# ps2st_mouse_v3.net
KiCad netlist of a schematic drawn in EAGLE
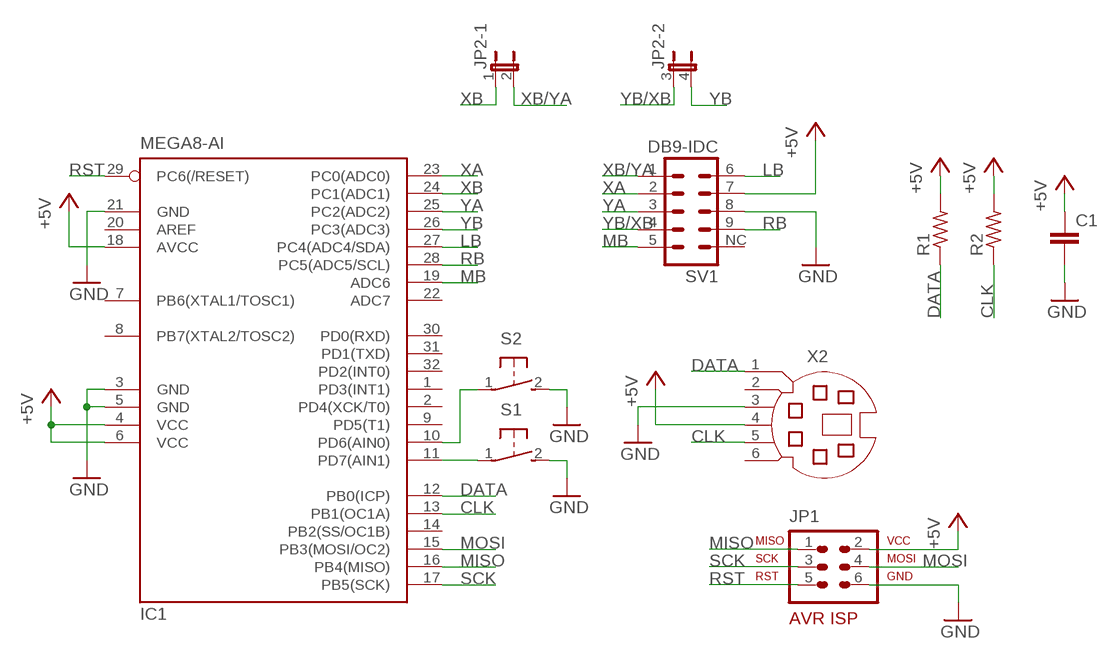
[diagram p0: schematic, sheet 1]

(export (version "E")
  (design (tool "Eeschema 10.0.6"))
  (components
    (comp (ref "C1")
      (value "C-EUC0805")
      (footprint "eagle-import:C0805")
      (libsource (lib "eagle-import") (part "C-EUC0805"))
    )
    (comp (ref "IC1")
      (value "MEGA8-AI")
      (footprint "eagle-import:TQFP32-08")
      (fields (field (name "MPN") "ATMEGA8-16AU"))
      (libsource (lib "eagle-import") (part "MEGA8-AI"))
    )
    (comp (ref "JP1")
      (value "AVR-ISP-6VERT")
      (footprint "eagle-import:AVR-ISP-6")
      (libsource (lib "eagle-import") (part "AVR-ISP-6VERT"))
    )
    (comp (ref "JP2")
      (value "JP2QE")
      (footprint "eagle-import:JP2Q")
      (libsource (lib "eagle-import") (part "JP2QE"))
    )
    (comp (ref "R1")
      (value "R-US_R0805")
      (footprint "eagle-import:R0805")
      (libsource (lib "eagle-import") (part "R-US_R0805"))
    )
    (comp (ref "R2")
      (value "R-US_R0805")
      (footprint "eagle-import:R0805")
      (libsource (lib "eagle-import") (part "R-US_R0805"))
    )
    (comp (ref "S1")
      (value "3X6SWITCH")
      (footprint "eagle-import:3X6")
      (libsource (lib "eagle-import") (part "3X6SWITCH"))
    )
    (comp (ref "S2")
      (value "3X6SWITCH")
      (footprint "eagle-import:3X6")
      (libsource (lib "eagle-import") (part "3X6SWITCH"))
    )
    (comp (ref "SV1")
      (value "DB9-IDC")
      (footprint "eagle-import:DB9")
      (libsource (lib "eagle-import") (part "DB9-IDC"))
    )
    (comp (ref "X2")
      (value "MD06SS")
      (footprint "eagle-import:MDIN06SS")
      (libsource (lib "eagle-import") (part "MD06SS"))
    )
  )
  (nets
    (net (code "1") (name "+5V") (class "Default")
      (node (ref "C1") (pin "1") (pinfunction "1_1") (pintype "passive"))
      (node (ref "IC1") (pin "18") (pinfunction "AVCC_18") (pintype "power_in"))
      (node (ref "IC1") (pin "4") (pinfunction "VCC_4") (pintype "power_in"))
      (node (ref "IC1") (pin "6") (pinfunction "VCC_6") (pintype "power_in"))
      (node (ref "JP1") (pin "2") (pinfunction "2_2") (pintype "passive"))
      (node (ref "R1") (pin "2") (pinfunction "2_2") (pintype "passive"))
      (node (ref "R2") (pin "2") (pinfunction "2_2") (pintype "passive"))
      (node (ref "SV1") (pin "7") (pinfunction "7_7") (pintype "passive"))
      (node (ref "X2") (pin "4") (pinfunction "4_4") (pintype "passive"))
    )
    (net (code "2") (name "/CLK") (class "Default")
      (node (ref "IC1") (pin "13") (pinfunction "PB1(OC1A)_13") (pintype "bidirectional"))
      (node (ref "R2") (pin "1") (pinfunction "1_1") (pintype "passive"))
      (node (ref "X2") (pin "5") (pinfunction "5_5") (pintype "passive"))
    )
    (net (code "3") (name "/DATA") (class "Default")
      (node (ref "IC1") (pin "12") (pinfunction "PB0(ICP)_12") (pintype "bidirectional"))
      (node (ref "R1") (pin "1") (pinfunction "1_1") (pintype "passive"))
      (node (ref "X2") (pin "1") (pinfunction "1_1") (pintype "passive"))
    )
    (net (code "4") (name "/LB") (class "Default")
      (node (ref "IC1") (pin "27") (pinfunction "PC4(ADC4/SDA)_27") (pintype "bidirectional"))
      (node (ref "SV1") (pin "6") (pinfunction "6_6") (pintype "passive"))
    )
    (net (code "5") (name "/MB") (class "Default")
      (node (ref "IC1") (pin "19") (pinfunction "ADC6_19") (pintype "bidirectional"))
      (node (ref "SV1") (pin "5") (pinfunction "5_5") (pintype "passive"))
    )
    (net (code "6") (name "/MISO") (class "Default")
      (node (ref "IC1") (pin "16") (pinfunction "PB4(MISO)_16") (pintype "bidirectional"))
      (node (ref "JP1") (pin "1") (pinfunction "1_1") (pintype "passive"))
    )
    (net (code "7") (name "/MOSI") (class "Default")
      (node (ref "IC1") (pin "15") (pinfunction "PB3(MOSI/OC2)_15") (pintype "bidirectional"))
      (node (ref "JP1") (pin "4") (pinfunction "4_4") (pintype "passive"))
    )
    (net (code "8") (name "/RB") (class "Default")
      (node (ref "IC1") (pin "28") (pinfunction "PC5(ADC5/SCL)_28") (pintype "bidirectional"))
      (node (ref "SV1") (pin "9") (pinfunction "9_9") (pintype "passive"))
    )
    (net (code "9") (name "/RST") (class "Default")
      (node (ref "IC1") (pin "29") (pinfunction "PC6(/RESET)_29") (pintype "bidirectional"))
      (node (ref "JP1") (pin "5") (pinfunction "5_5") (pintype "passive"))
    )
    (net (code "10") (name "/SCK") (class "Default")
      (node (ref "IC1") (pin "17") (pinfunction "PB5(SCK)_17") (pintype "bidirectional"))
      (node (ref "JP1") (pin "3") (pinfunction "3_3") (pintype "passive"))
    )
    (net (code "11") (name "/XA") (class "Default")
      (node (ref "IC1") (pin "23") (pinfunction "PC0(ADC0)_23") (pintype "bidirectional"))
      (node (ref "SV1") (pin "2") (pinfunction "2_2") (pintype "passive"))
    )
    (net (code "12") (name "/XB") (class "Default")
      (node (ref "IC1") (pin "24") (pinfunction "PC1(ADC1)_24") (pintype "bidirectional"))
      (node (ref "JP2") (pin "1") (pinfunction "1_1") (pintype "passive"))
    )
    (net (code "13") (name "/XB{slash}YA") (class "Default")
      (node (ref "JP2") (pin "2") (pinfunction "2_2") (pintype "passive"))
      (node (ref "SV1") (pin "1") (pinfunction "1_1") (pintype "passive"))
    )
    (net (code "14") (name "/YA") (class "Default")
      (node (ref "IC1") (pin "25") (pinfunction "PC2(ADC2)_25") (pintype "bidirectional"))
      (node (ref "SV1") (pin "3") (pinfunction "3_3") (pintype "passive"))
    )
    (net (code "15") (name "/YB") (class "Default")
      (node (ref "IC1") (pin "26") (pinfunction "PC3(ADC3)_26") (pintype "bidirectional"))
      (node (ref "JP2") (pin "4") (pinfunction "2_4") (pintype "passive"))
    )
    (net (code "16") (name "/YB{slash}XB") (class "Default")
      (node (ref "JP2") (pin "3") (pinfunction "1_3") (pintype "passive"))
      (node (ref "SV1") (pin "4") (pinfunction "4_4") (pintype "passive"))
    )
    (net (code "17") (name "GND") (class "Default")
      (node (ref "C1") (pin "2") (pinfunction "2_2") (pintype "passive"))
      (node (ref "IC1") (pin "21") (pinfunction "GND_21") (pintype "power_in"))
      (node (ref "IC1") (pin "3") (pinfunction "GND_3") (pintype "power_in"))
      (node (ref "IC1") (pin "5") (pinfunction "GND_5") (pintype "power_in"))
      (node (ref "JP1") (pin "6") (pinfunction "6_6") (pintype "passive"))
      (node (ref "S1") (pin "2") (pinfunction "S_2") (pintype "passive"))
      (node (ref "S2") (pin "2") (pinfunction "S_2") (pintype "passive"))
      (node (ref "SV1") (pin "8") (pinfunction "8_8") (pintype "passive"))
      (node (ref "X2") (pin "3") (pinfunction "3_3") (pintype "passive"))
    )
    (net (code "18") (name "Net-(IC1-PD6(AIN0))") (class "Default")
      (node (ref "IC1") (pin "10") (pinfunction "PD6(AIN0)_10") (pintype "bidirectional"))
      (node (ref "S2") (pin "1") (pinfunction "P_1") (pintype "passive"))
    )
    (net (code "19") (name "Net-(IC1-PD7(AIN1))") (class "Default")
      (node (ref "IC1") (pin "11") (pinfunction "PD7(AIN1)_11") (pintype "bidirectional"))
      (node (ref "S1") (pin "1") (pinfunction "P_1") (pintype "passive"))
    )
    (net (code "20") (name "unconnected-(IC1-ADC7-Pad22)") (class "Default")
      (node (ref "IC1") (pin "22") (pinfunction "ADC7_22") (pintype "bidirectional"))
    )
    (net (code "21") (name "unconnected-(IC1-AREF-Pad20)") (class "Default")
      (node (ref "IC1") (pin "20") (pinfunction "AREF_20") (pintype "passive"))
    )
    (net (code "22") (name "unconnected-(IC1-PB2(SS{slash}OC1B)-Pad14)") (class "Default")
      (node (ref "IC1") (pin "14") (pinfunction "PB2(SS/OC1B)_14") (pintype "bidirectional"))
    )
    (net (code "23") (name "unconnected-(IC1-PB6(XTAL1{slash}TOSC1)-Pad7)") (class "Default")
      (node (ref "IC1") (pin "7") (pinfunction "PB6(XTAL1/TOSC1)_7") (pintype "bidirectional"))
    )
    (net (code "24") (name "unconnected-(IC1-PB7(XTAL2{slash}TOSC2)-Pad8)") (class "Default")
      (node (ref "IC1") (pin "8") (pinfunction "PB7(XTAL2/TOSC2)_8") (pintype "bidirectional"))
    )
    (net (code "25") (name "unconnected-(IC1-PD0(RXD)-Pad30)") (class "Default")
      (node (ref "IC1") (pin "30") (pinfunction "PD0(RXD)_30") (pintype "bidirectional"))
    )
    (net (code "26") (name "unconnected-(IC1-PD1(TXD)-Pad31)") (class "Default")
      (node (ref "IC1") (pin "31") (pinfunction "PD1(TXD)_31") (pintype "bidirectional"))
    )
    (net (code "27") (name "unconnected-(IC1-PD2(INT0)-Pad32)") (class "Default")
      (node (ref "IC1") (pin "32") (pinfunction "PD2(INT0)_32") (pintype "bidirectional"))
    )
    (net (code "28") (name "unconnected-(IC1-PD3(INT1)-Pad1)") (class "Default")
      (node (ref "IC1") (pin "1") (pinfunction "PD3(INT1)_1") (pintype "bidirectional"))
    )
    (net (code "29") (name "unconnected-(IC1-PD4(XCK{slash}T0)-Pad2)") (class "Default")
      (node (ref "IC1") (pin "2") (pinfunction "PD4(XCK/T0)_2") (pintype "bidirectional"))
    )
    (net (code "30") (name "unconnected-(IC1-PD5(T1)-Pad9)") (class "Default")
      (node (ref "IC1") (pin "9") (pinfunction "PD5(T1)_9") (pintype "bidirectional"))
    )
    (net (code "31") (name "unconnected-(SV1-PadNC)") (class "Default")
      (node (ref "SV1") (pin "NC") (pinfunction "NC_NC") (pintype "passive"))
    )
    (net (code "32") (name "unconnected-(X2-Pad2)") (class "Default")
      (node (ref "X2") (pin "2") (pinfunction "2_2") (pintype "passive"))
    )
    (net (code "33") (name "unconnected-(X2-Pad6)") (class "Default")
      (node (ref "X2") (pin "6") (pinfunction "6_6") (pintype "passive"))
    )
  )
)
